# Borealis.net
KiCad netlist of a schematic drawn in EAGLE
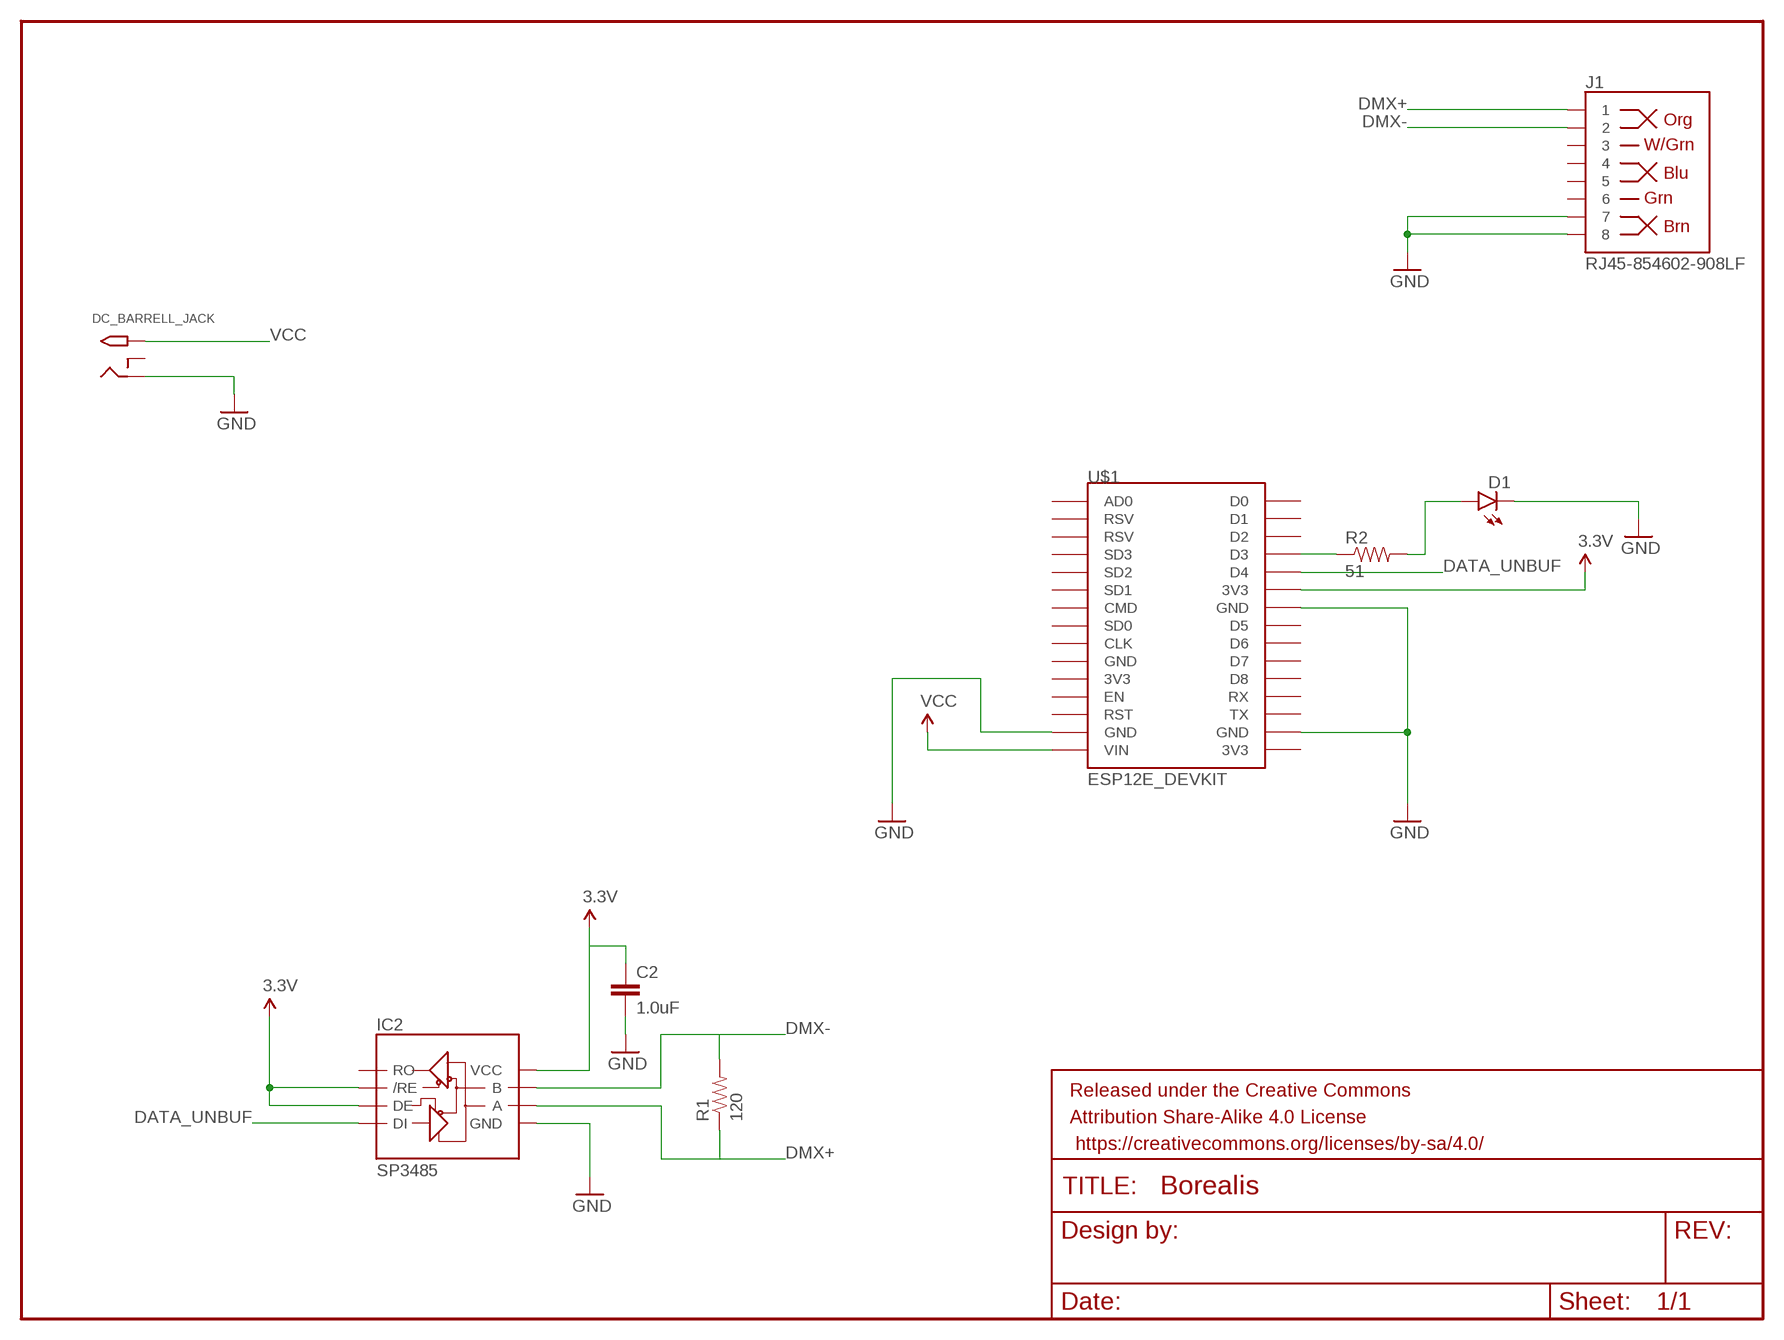
[diagram p0: schematic, sheet 1]

(export (version "E")
  (design (tool "Eeschema 10.0.6"))
  (components
    (comp (ref "C2")
      (value "1.0uF")
      (footprint "eagle-import:0603-CAP")
      (libsource (lib "eagle-import") (part "1.0UF-16V-10%(0603)"))
    )
    (comp (ref "D1")
      (value "LED1206-BOTTOM")
      (footprint "eagle-import:LED-1206-BOTTOM")
      (libsource (lib "eagle-import") (part "LED1206-BOTTOM"))
    )
    (comp (ref "DC_BARRELL_JACK")
      (value "2.1MMJACKTHM")
      (footprint "eagle-import:PJ-102A")
      (libsource (lib "eagle-import") (part "2.1MMJACKTHM"))
    )
    (comp (ref "FRAME1")
      (value "FRAME-LETTERNO_PACKAGE")
      (footprint "eagle-import:DUMMY")
      (fields (field (name "DESIGNER") "Nobody"))
      (libsource (lib "eagle-import") (part "FRAME-LETTERNO_PACKAGE"))
    )
    (comp (ref "IC2")
      (value "SP3485")
      (footprint "eagle-import:SO08")
      (libsource (lib "eagle-import") (part "RS485SOIC"))
    )
    (comp (ref "J1")
      (value "RJ45-854602-908LF")
      (footprint "eagle-import:RJ45-GREG")
      (libsource (lib "eagle-import") (part "RJ45-854602-908LF"))
    )
    (comp (ref "R1")
      (value "120")
      (footprint "eagle-import:0603-RES")
      (libsource (lib "eagle-import") (part "RESISTOR0603"))
    )
    (comp (ref "R2")
      (value "51")
      (footprint "eagle-import:0603-RES")
      (libsource (lib "eagle-import") (part "RESISTOR0603-RES"))
    )
    (comp (ref "U$1")
      (value "ESP12E_DEVKIT")
      (footprint "eagle-import:DEV_LAYOUT")
      (libsource (lib "eagle-import") (part "ESP12E_DEVKIT"))
    )
  )
  (nets
    (net (code "1") (name "/DATA_UNBUF") (class "Default")
      (node (ref "IC2") (pin "4") (pinfunction "DI_4") (pintype "bidirectional"))
      (node (ref "U$1") (pin "D4") (pinfunction "D4_D4") (pintype "bidirectional"))
    )
    (net (code "2") (name "/DMX+") (class "Default")
      (node (ref "IC2") (pin "6") (pinfunction "A_6") (pintype "bidirectional"))
      (node (ref "J1") (pin "1") (pinfunction "1_1") (pintype "bidirectional"))
      (node (ref "R1") (pin "1") (pinfunction "1_1") (pintype "passive"))
    )
    (net (code "3") (name "/DMX-") (class "Default")
      (node (ref "IC2") (pin "7") (pinfunction "B_7") (pintype "bidirectional"))
      (node (ref "J1") (pin "2") (pinfunction "2_2") (pintype "bidirectional"))
      (node (ref "R1") (pin "2") (pinfunction "2_2") (pintype "passive"))
    )
    (net (code "4") (name "3.3V") (class "Default")
      (node (ref "C2") (pin "1") (pinfunction "1_1") (pintype "passive"))
      (node (ref "IC2") (pin "2") (pinfunction "/RE_2") (pintype "bidirectional"))
      (node (ref "IC2") (pin "3") (pinfunction "DE_3") (pintype "bidirectional"))
      (node (ref "IC2") (pin "8") (pinfunction "VCC_8") (pintype "bidirectional"))
      (node (ref "U$1") (pin "3V3@1") (pinfunction "3V3_3V3@1") (pintype "bidirectional"))
    )
    (net (code "5") (name "GND") (class "Default")
      (node (ref "C2") (pin "2") (pinfunction "2_2") (pintype "passive"))
      (node (ref "D1") (pin "C") (pinfunction "C_C") (pintype "passive"))
      (node (ref "DC_BARRELL_JACK") (pin "RING") (pinfunction "RING_RING") (pintype "bidirectional"))
      (node (ref "IC2") (pin "5") (pinfunction "GND_5") (pintype "bidirectional"))
      (node (ref "J1") (pin "7") (pinfunction "7_7") (pintype "bidirectional"))
      (node (ref "J1") (pin "8") (pinfunction "8_8") (pintype "bidirectional"))
      (node (ref "U$1") (pin "GND@1") (pinfunction "GND_GND@1") (pintype "bidirectional"))
      (node (ref "U$1") (pin "GND@2") (pinfunction "GND_GND@2") (pintype "bidirectional"))
      (node (ref "U$1") (pin "GND@3") (pinfunction "GND_GND@3") (pintype "bidirectional"))
    )
    (net (code "6") (name "Net-(D1-PadA)") (class "Default")
      (node (ref "D1") (pin "A") (pinfunction "A_A") (pintype "passive"))
      (node (ref "R2") (pin "2") (pinfunction "2_2") (pintype "passive"))
    )
    (net (code "7") (name "Net-(R2-Pad1)") (class "Default")
      (node (ref "R2") (pin "1") (pinfunction "1_1") (pintype "passive"))
      (node (ref "U$1") (pin "D3") (pinfunction "D3_D3") (pintype "bidirectional"))
    )
    (net (code "8") (name "VCC") (class "Default")
      (node (ref "DC_BARRELL_JACK") (pin "TIP") (pinfunction "TIP_TIP") (pintype "bidirectional"))
      (node (ref "U$1") (pin "VIN") (pinfunction "VIN_VIN") (pintype "bidirectional"))
    )
    (net (code "9") (name "unconnected-(DC_BARRELL_JACK-PadRING_SW)") (class "Default")
      (node (ref "DC_BARRELL_JACK") (pin "RING_SW") (pinfunction "RING_SW_RING_SW") (pintype "bidirectional"))
    )
    (net (code "10") (name "unconnected-(IC2-RO-Pad1)") (class "Default")
      (node (ref "IC2") (pin "1") (pinfunction "RO_1") (pintype "bidirectional"))
    )
    (net (code "11") (name "unconnected-(J1-Pad3)") (class "Default")
      (node (ref "J1") (pin "3") (pinfunction "3_3") (pintype "bidirectional"))
    )
    (net (code "12") (name "unconnected-(J1-Pad4)") (class "Default")
      (node (ref "J1") (pin "4") (pinfunction "4_4") (pintype "bidirectional"))
    )
    (net (code "13") (name "unconnected-(J1-Pad5)") (class "Default")
      (node (ref "J1") (pin "5") (pinfunction "5_5") (pintype "bidirectional"))
    )
    (net (code "14") (name "unconnected-(J1-Pad6)") (class "Default")
      (node (ref "J1") (pin "6") (pinfunction "6_6") (pintype "bidirectional"))
    )
    (net (code "15") (name "unconnected-(U$1-3V3-Pad3V3@0)") (class "Default")
      (node (ref "U$1") (pin "3V3@0") (pinfunction "3V3_3V3@0") (pintype "bidirectional"))
    )
    (net (code "16") (name "unconnected-(U$1-3V3-Pad3V3@2)") (class "Default")
      (node (ref "U$1") (pin "3V3@2") (pinfunction "3V3_3V3@2") (pintype "bidirectional"))
    )
    (net (code "17") (name "unconnected-(U$1-GND-PadGND@0)") (class "Default")
      (node (ref "U$1") (pin "GND@0") (pinfunction "GND_GND@0") (pintype "bidirectional"))
    )
    (net (code "18") (name "unconnected-(U$1-PadAD0)") (class "Default")
      (node (ref "U$1") (pin "AD0") (pinfunction "AD0_AD0") (pintype "bidirectional"))
    )
    (net (code "19") (name "unconnected-(U$1-PadCLK)") (class "Default")
      (node (ref "U$1") (pin "CLK") (pinfunction "CLK_CLK") (pintype "bidirectional"))
    )
    (net (code "20") (name "unconnected-(U$1-PadCMD)") (class "Default")
      (node (ref "U$1") (pin "CMD") (pinfunction "CMD_CMD") (pintype "bidirectional"))
    )
    (net (code "21") (name "unconnected-(U$1-PadD0)") (class "Default")
      (node (ref "U$1") (pin "D0") (pinfunction "D0_D0") (pintype "bidirectional"))
    )
    (net (code "22") (name "unconnected-(U$1-PadD1)") (class "Default")
      (node (ref "U$1") (pin "D1") (pinfunction "D1_D1") (pintype "bidirectional"))
    )
    (net (code "23") (name "unconnected-(U$1-PadD2)") (class "Default")
      (node (ref "U$1") (pin "D2") (pinfunction "D2_D2") (pintype "bidirectional"))
    )
    (net (code "24") (name "unconnected-(U$1-PadD5)") (class "Default")
      (node (ref "U$1") (pin "D5") (pinfunction "D5_D5") (pintype "bidirectional"))
    )
    (net (code "25") (name "unconnected-(U$1-PadD6)") (class "Default")
      (node (ref "U$1") (pin "D6") (pinfunction "D6_D6") (pintype "bidirectional"))
    )
    (net (code "26") (name "unconnected-(U$1-PadD7)") (class "Default")
      (node (ref "U$1") (pin "D7") (pinfunction "D7_D7") (pintype "bidirectional"))
    )
    (net (code "27") (name "unconnected-(U$1-PadD8)") (class "Default")
      (node (ref "U$1") (pin "D8") (pinfunction "D8_D8") (pintype "bidirectional"))
    )
    (net (code "28") (name "unconnected-(U$1-PadEN)") (class "Default")
      (node (ref "U$1") (pin "EN") (pinfunction "EN_EN") (pintype "bidirectional"))
    )
    (net (code "29") (name "unconnected-(U$1-PadRST)") (class "Default")
      (node (ref "U$1") (pin "RST") (pinfunction "RST_RST") (pintype "bidirectional"))
    )
    (net (code "30") (name "unconnected-(U$1-PadRX)") (class "Default")
      (node (ref "U$1") (pin "RX") (pinfunction "RX_RX") (pintype "bidirectional"))
    )
    (net (code "31") (name "unconnected-(U$1-PadSD0)") (class "Default")
      (node (ref "U$1") (pin "SD0") (pinfunction "SD0_SD0") (pintype "bidirectional"))
    )
    (net (code "32") (name "unconnected-(U$1-PadSD1)") (class "Default")
      (node (ref "U$1") (pin "SD1") (pinfunction "SD1_SD1") (pintype "bidirectional"))
    )
    (net (code "33") (name "unconnected-(U$1-PadSD2)") (class "Default")
      (node (ref "U$1") (pin "SD2") (pinfunction "SD2_SD2") (pintype "bidirectional"))
    )
    (net (code "34") (name "unconnected-(U$1-PadSD3)") (class "Default")
      (node (ref "U$1") (pin "SD3") (pinfunction "SD3_SD3") (pintype "bidirectional"))
    )
    (net (code "35") (name "unconnected-(U$1-PadTX)") (class "Default")
      (node (ref "U$1") (pin "TX") (pinfunction "TX_TX") (pintype "bidirectional"))
    )
    (net (code "36") (name "unconnected-(U$1-RSV-PadRSV@0)") (class "Default")
      (node (ref "U$1") (pin "RSV@0") (pinfunction "RSV_RSV@0") (pintype "bidirectional"))
    )
    (net (code "37") (name "unconnected-(U$1-RSV-PadRSV@1)") (class "Default")
      (node (ref "U$1") (pin "RSV@1") (pinfunction "RSV_RSV@1") (pintype "bidirectional"))
    )
  )
)
